# PI_SCH_FPC.net
KiCad netlist of a schematic drawn in EasyEDA
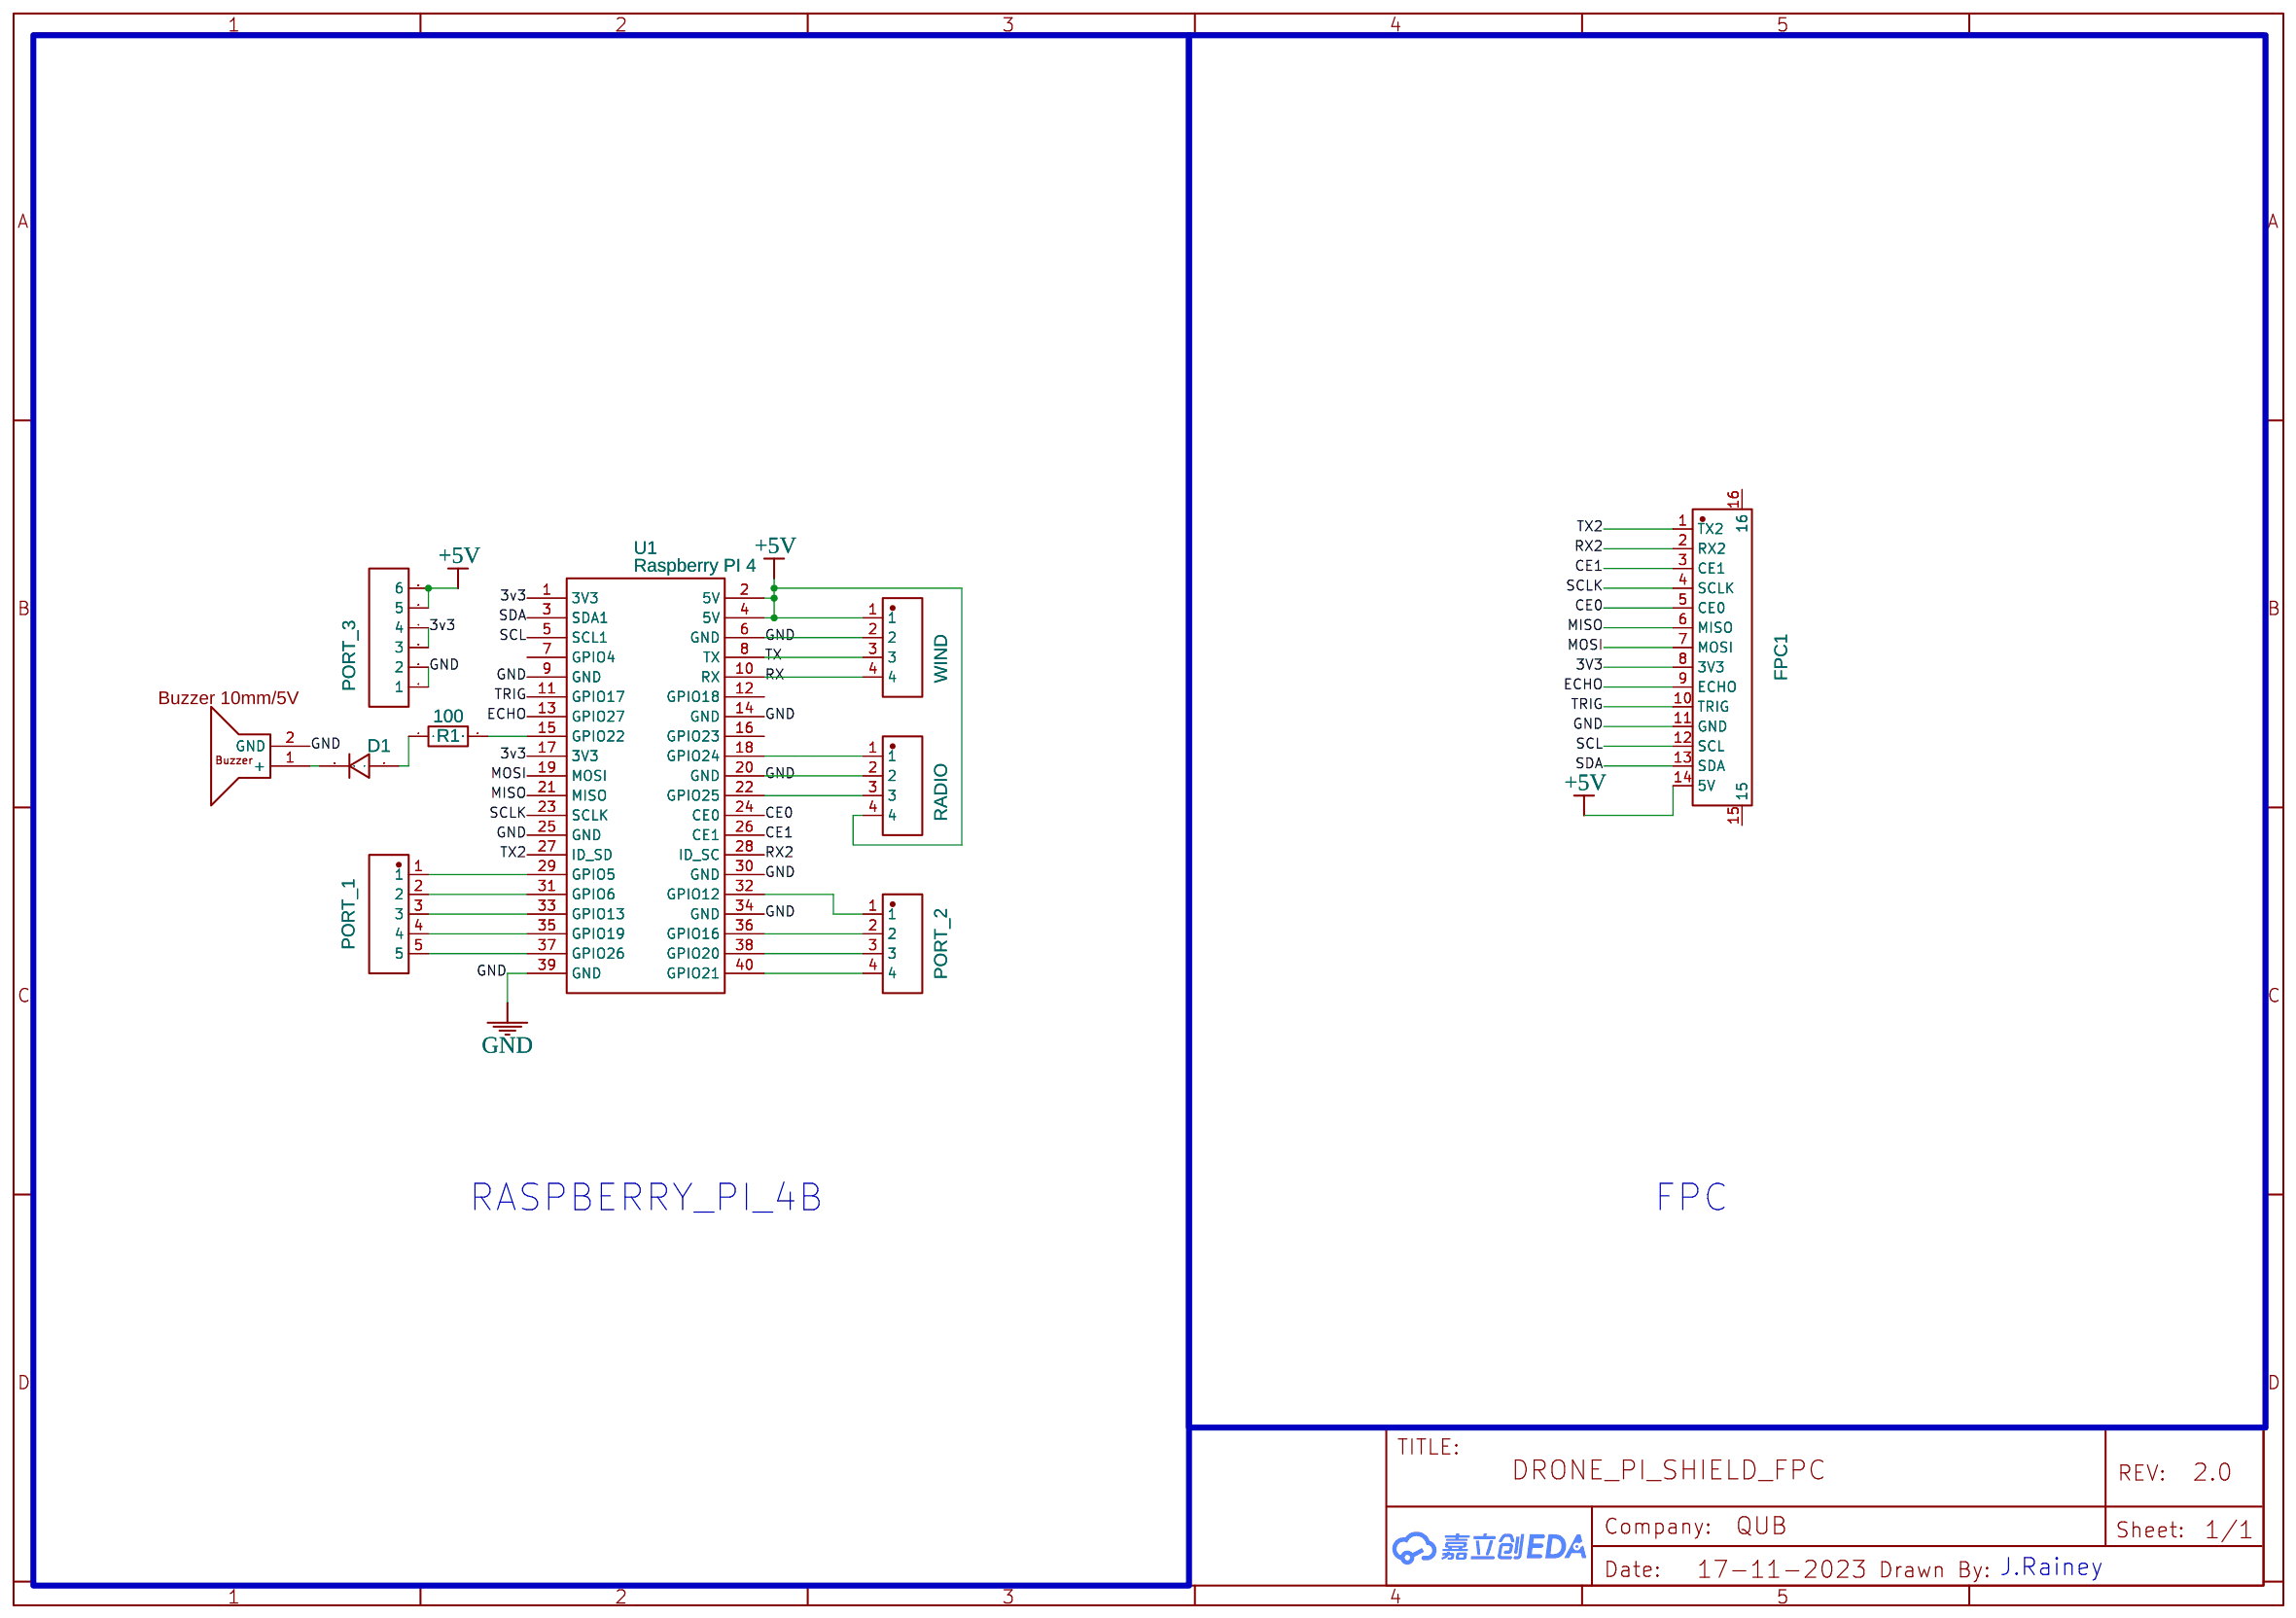
[diagram p0: schematic sheet]

(export (version "E")
  (design (tool "Eeschema 10.0.6"))
  (components
    (comp (ref "BUZZER1")
      (value "Buzzer 10mm/5V")
      (fields (field (name "BOM_Manufacturer Part") "BUZZER"))
      (libsource (lib "") (part "Buzzer 10mm/5V"))
    )
    (comp (ref "D1")
      (value "1N4448")
      (fields (field (name "Manufacturer") "ST(先科)"))
      (libsource (lib "") (part "1N4448"))
    )
    (comp (ref "FPC1")
      (value "1.0K-FX-14PWB")
      (fields (field (name "Manufacturer") "HDGC(华德共创)"))
      (libsource (lib "") (part "1.0K-FX-14PWB"))
    )
    (comp (ref "PORT_1")
      (value "PZ254V-11-05P")
      (fields (field (name "BOM_Supplier Part") "C492404"))
      (libsource (lib "") (part "PZ254V-11-05P"))
    )
    (comp (ref "PORT_2")
      (value "PZ254V-11-04P")
      (fields (field (name "BOM_Supplier Part") "C492403"))
      (libsource (lib "") (part "PZ254V-11-04P_1"))
    )
    (comp (ref "PORT_3")
      (value "HEADER-MALE-2.54_1X6")
      (fields
        (field (name "BOM_Manufacturer Part") "Header-Male-2.54_1x6")
        (field (name "BOM_Supplier Part") "C37208")
      )
      (libsource (lib "") (part "HEADER-MALE-2.54_1X6"))
    )
    (comp (ref "R1") (value "100") (libsource (lib "") (part "R_AXIAL-0.4_EU")))
    (comp (ref "RADIO")
      (value "PZ254V-11-04P")
      (fields (field (name "BOM_Supplier Part") "C492403"))
      (libsource (lib "") (part "PZ254V-11-04P_2"))
    )
    (comp (ref "U1") (value "Raspberry PI 4") (libsource (lib "") (part "Raspberry PI 4")))
    (comp (ref "WIND")
      (value "PZ254V-11-04P")
      (fields (field (name "BOM_Supplier Part") "C492403"))
      (libsource (lib "") (part "PZ254V-11-04P"))
    )
  )
  (nets
    (net (code "1") (name "+5V") (class "Default")
      (node (ref "FPC1") (pin "14") (pinfunction "5V_14") (pintype "unspecified"))
      (node (ref "PORT_3") (pin "5") (pinfunction "5_5") (pintype "input"))
      (node (ref "PORT_3") (pin "6") (pinfunction "6_6") (pintype "input"))
      (node (ref "RADIO") (pin "4") (pinfunction "4_4") (pintype "unspecified"))
      (node (ref "U1") (pin "2") (pinfunction "5V_2") (pintype "unspecified"))
      (node (ref "U1") (pin "4") (pinfunction "5V_4") (pintype "unspecified"))
      (node (ref "WIND") (pin "1") (pinfunction "1_1") (pintype "unspecified"))
    )
    (net (code "2") (name "/3V3") (class "Default")
      (node (ref "FPC1") (pin "8") (pinfunction "3V3_8") (pintype "unspecified"))
    )
    (net (code "3") (name "/3v3") (class "Default")
      (node (ref "PORT_3") (pin "3") (pinfunction "3_3") (pintype "input"))
      (node (ref "PORT_3") (pin "4") (pinfunction "4_4") (pintype "input"))
      (node (ref "U1") (pin "1") (pinfunction "3V3_1") (pintype "unspecified"))
      (node (ref "U1") (pin "17") (pinfunction "3V3_17") (pintype "unspecified"))
    )
    (net (code "4") (name "/CE0") (class "Default")
      (node (ref "FPC1") (pin "5") (pinfunction "CE0_5") (pintype "unspecified"))
      (node (ref "U1") (pin "24") (pinfunction "CE0_24") (pintype "unspecified"))
    )
    (net (code "5") (name "/CE1") (class "Default")
      (node (ref "FPC1") (pin "3") (pinfunction "CE1_3") (pintype "unspecified"))
      (node (ref "U1") (pin "26") (pinfunction "CE1_26") (pintype "unspecified"))
    )
    (net (code "6") (name "/ECHO") (class "Default")
      (node (ref "FPC1") (pin "9") (pinfunction "ECHO_9") (pintype "unspecified"))
      (node (ref "U1") (pin "13") (pinfunction "GPIO27_13") (pintype "unspecified"))
    )
    (net (code "7") (name "/MISO") (class "Default")
      (node (ref "FPC1") (pin "6") (pinfunction "MISO_6") (pintype "unspecified"))
      (node (ref "U1") (pin "21") (pinfunction "MISO_21") (pintype "unspecified"))
    )
    (net (code "8") (name "/MOSI") (class "Default")
      (node (ref "FPC1") (pin "7") (pinfunction "MOSI_7") (pintype "unspecified"))
      (node (ref "U1") (pin "19") (pinfunction "MOSI_19") (pintype "unspecified"))
    )
    (net (code "9") (name "/RX") (class "Default")
      (node (ref "U1") (pin "10") (pinfunction "RX_10") (pintype "unspecified"))
      (node (ref "WIND") (pin "4") (pinfunction "4_4") (pintype "unspecified"))
    )
    (net (code "10") (name "/RX2") (class "Default")
      (node (ref "FPC1") (pin "2") (pinfunction "RX2_2") (pintype "unspecified"))
      (node (ref "U1") (pin "28") (pinfunction "ID_SC_28") (pintype "unspecified"))
    )
    (net (code "11") (name "/SCL") (class "Default")
      (node (ref "FPC1") (pin "12") (pinfunction "SCL_12") (pintype "unspecified"))
      (node (ref "U1") (pin "5") (pinfunction "SCL1_5") (pintype "unspecified"))
    )
    (net (code "12") (name "/SCLK") (class "Default")
      (node (ref "FPC1") (pin "4") (pinfunction "SCLK_4") (pintype "unspecified"))
      (node (ref "U1") (pin "23") (pinfunction "SCLK_23") (pintype "unspecified"))
    )
    (net (code "13") (name "/SDA") (class "Default")
      (node (ref "FPC1") (pin "13") (pinfunction "SDA_13") (pintype "unspecified"))
      (node (ref "U1") (pin "3") (pinfunction "SDA1_3") (pintype "unspecified"))
    )
    (net (code "14") (name "/TRIG") (class "Default")
      (node (ref "FPC1") (pin "10") (pinfunction "TRIG_10") (pintype "unspecified"))
      (node (ref "U1") (pin "11") (pinfunction "GPIO17_11") (pintype "unspecified"))
    )
    (net (code "15") (name "/TX") (class "Default")
      (node (ref "U1") (pin "8") (pinfunction "TX_8") (pintype "unspecified"))
      (node (ref "WIND") (pin "3") (pinfunction "3_3") (pintype "unspecified"))
    )
    (net (code "16") (name "/TX2") (class "Default")
      (node (ref "FPC1") (pin "1") (pinfunction "TX2_1") (pintype "unspecified"))
      (node (ref "U1") (pin "27") (pinfunction "ID_SD_27") (pintype "unspecified"))
    )
    (net (code "17") (name "GND") (class "Default")
      (node (ref "BUZZER1") (pin "2") (pinfunction "GND_2") (pintype "unspecified"))
      (node (ref "FPC1") (pin "11") (pinfunction "GND_11") (pintype "unspecified"))
      (node (ref "PORT_3") (pin "1") (pinfunction "1_1") (pintype "input"))
      (node (ref "PORT_3") (pin "2") (pinfunction "2_2") (pintype "input"))
      (node (ref "RADIO") (pin "2") (pinfunction "2_2") (pintype "unspecified"))
      (node (ref "U1") (pin "14") (pinfunction "GND_14") (pintype "unspecified"))
      (node (ref "U1") (pin "20") (pinfunction "GND_20") (pintype "unspecified"))
      (node (ref "U1") (pin "25") (pinfunction "GND_25") (pintype "unspecified"))
      (node (ref "U1") (pin "30") (pinfunction "GND_30") (pintype "unspecified"))
      (node (ref "U1") (pin "34") (pinfunction "GND_34") (pintype "unspecified"))
      (node (ref "U1") (pin "39") (pinfunction "GND_39") (pintype "unspecified"))
      (node (ref "U1") (pin "6") (pinfunction "GND_6") (pintype "unspecified"))
      (node (ref "U1") (pin "9") (pinfunction "GND_9") (pintype "unspecified"))
      (node (ref "WIND") (pin "2") (pinfunction "2_2") (pintype "unspecified"))
    )
    (net (code "18") (name "Net-(BUZZER1-+)") (class "Default")
      (node (ref "BUZZER1") (pin "1") (pinfunction "+_1") (pintype "unspecified"))
      (node (ref "D1") (pin "2") (pinfunction "K_2") (pintype "unspecified"))
    )
    (net (code "19") (name "Net-(D1-A)") (class "Default")
      (node (ref "D1") (pin "1") (pinfunction "A_1") (pintype "unspecified"))
      (node (ref "R1") (pin "1") (pinfunction "1_1") (pintype "unspecified"))
    )
    (net (code "20") (name "Net-(U1-GPIO5)") (class "Default")
      (node (ref "PORT_1") (pin "1") (pinfunction "1_1") (pintype "unspecified"))
      (node (ref "U1") (pin "29") (pinfunction "GPIO5_29") (pintype "unspecified"))
    )
    (net (code "21") (name "Net-(U1-GPIO6)") (class "Default")
      (node (ref "PORT_1") (pin "2") (pinfunction "2_2") (pintype "unspecified"))
      (node (ref "U1") (pin "31") (pinfunction "GPIO6_31") (pintype "unspecified"))
    )
    (net (code "22") (name "Net-(U1-GPIO12)") (class "Default")
      (node (ref "PORT_2") (pin "1") (pinfunction "1_1") (pintype "unspecified"))
      (node (ref "U1") (pin "32") (pinfunction "GPIO12_32") (pintype "unspecified"))
    )
    (net (code "23") (name "Net-(U1-GPIO13)") (class "Default")
      (node (ref "PORT_1") (pin "3") (pinfunction "3_3") (pintype "unspecified"))
      (node (ref "U1") (pin "33") (pinfunction "GPIO13_33") (pintype "unspecified"))
    )
    (net (code "24") (name "Net-(U1-GPIO16)") (class "Default")
      (node (ref "PORT_2") (pin "2") (pinfunction "2_2") (pintype "unspecified"))
      (node (ref "U1") (pin "36") (pinfunction "GPIO16_36") (pintype "unspecified"))
    )
    (net (code "25") (name "Net-(U1-GPIO19)") (class "Default")
      (node (ref "PORT_1") (pin "4") (pinfunction "4_4") (pintype "unspecified"))
      (node (ref "U1") (pin "35") (pinfunction "GPIO19_35") (pintype "unspecified"))
    )
    (net (code "26") (name "Net-(U1-GPIO20)") (class "Default")
      (node (ref "PORT_2") (pin "3") (pinfunction "3_3") (pintype "unspecified"))
      (node (ref "U1") (pin "38") (pinfunction "GPIO20_38") (pintype "unspecified"))
    )
    (net (code "27") (name "Net-(U1-GPIO21)") (class "Default")
      (node (ref "PORT_2") (pin "4") (pinfunction "4_4") (pintype "unspecified"))
      (node (ref "U1") (pin "40") (pinfunction "GPIO21_40") (pintype "unspecified"))
    )
    (net (code "28") (name "Net-(U1-GPIO22)") (class "Default")
      (node (ref "R1") (pin "2") (pinfunction "2_2") (pintype "unspecified"))
      (node (ref "U1") (pin "15") (pinfunction "GPIO22_15") (pintype "unspecified"))
    )
    (net (code "29") (name "Net-(U1-GPIO24)") (class "Default")
      (node (ref "RADIO") (pin "1") (pinfunction "1_1") (pintype "unspecified"))
      (node (ref "U1") (pin "18") (pinfunction "GPIO24_18") (pintype "unspecified"))
    )
    (net (code "30") (name "Net-(U1-GPIO25)") (class "Default")
      (node (ref "RADIO") (pin "3") (pinfunction "3_3") (pintype "unspecified"))
      (node (ref "U1") (pin "22") (pinfunction "GPIO25_22") (pintype "unspecified"))
    )
    (net (code "31") (name "Net-(U1-GPIO26)") (class "Default")
      (node (ref "PORT_1") (pin "5") (pinfunction "5_5") (pintype "unspecified"))
      (node (ref "U1") (pin "37") (pinfunction "GPIO26_37") (pintype "unspecified"))
    )
    (net (code "32") (name "unconnected-(FPC1-Pad15)") (class "Default")
      (node (ref "FPC1") (pin "15") (pinfunction "15_15") (pintype "unspecified"))
    )
    (net (code "33") (name "unconnected-(FPC1-Pad16)") (class "Default")
      (node (ref "FPC1") (pin "16") (pinfunction "16_16") (pintype "unspecified"))
    )
    (net (code "34") (name "unconnected-(U1-GPIO4-Pad7)") (class "Default")
      (node (ref "U1") (pin "7") (pinfunction "GPIO4_7") (pintype "unspecified"))
    )
    (net (code "35") (name "unconnected-(U1-GPIO18-Pad12)") (class "Default")
      (node (ref "U1") (pin "12") (pinfunction "GPIO18_12") (pintype "unspecified"))
    )
    (net (code "36") (name "unconnected-(U1-GPIO23-Pad16)") (class "Default")
      (node (ref "U1") (pin "16") (pinfunction "GPIO23_16") (pintype "unspecified"))
    )
  )
)
